# Sheet7.net
KiCad netlist of a schematic drawn in Altium Designer
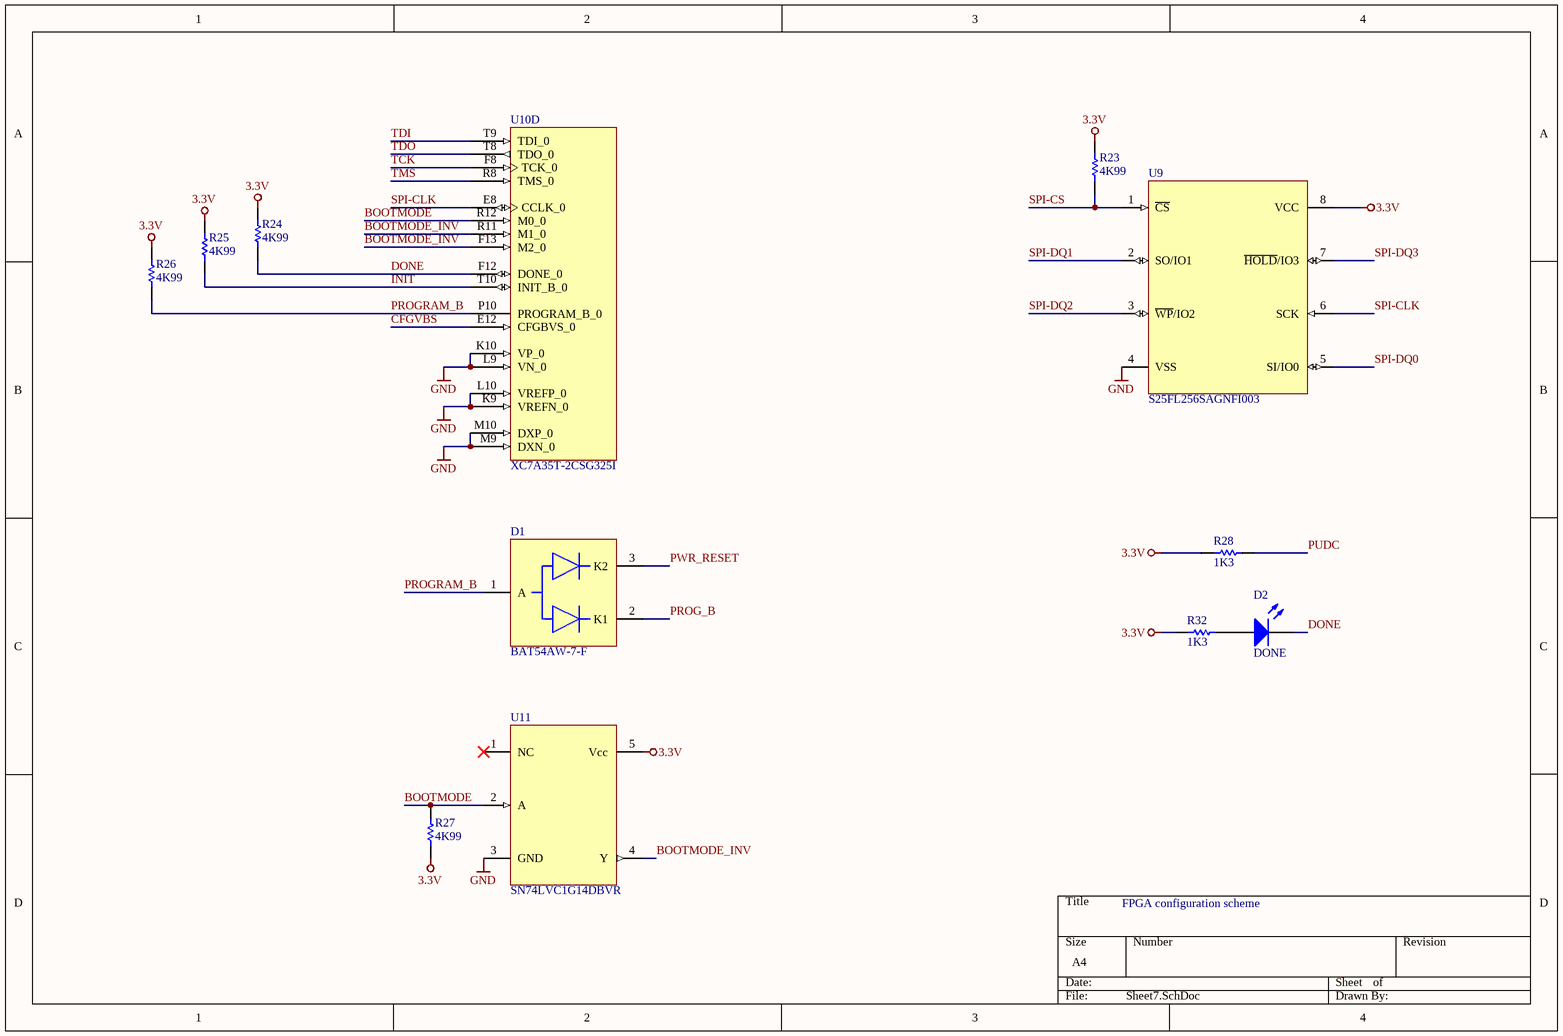
[diagram p0: Sheet7.SchDoc]

(export (version "E")
  (design (tool "Eeschema 10.0.6"))
  (components
    (comp (ref "D1")
      (value "BAT54AW-7-F")
      (footprint "BAT54AW-7-F")
      (description "SCHOTTKY BARRIER DIODE")
      (libsource (lib "Integrated_Library") (part "BAT54AW-7-F"))
    )
    (comp (ref "D2")
      (value "DONE")
      (footprint "LEDC2012X10N")
      (description "SMD chip LED")
      (libsource (lib "Integrated_Library") (part "LED0805"))
    )
    (comp (ref "R23")
      (value "4K99")
      (footprint "RESC1005X05N")
      (description "Ceramic Chip Resistor")
      (libsource (lib "Integrated_Library") (part "R0402"))
    )
    (comp (ref "R24")
      (value "4K99")
      (footprint "RESC1005X05N")
      (description "Ceramic Chip Resistor")
      (libsource (lib "Integrated_Library") (part "R0402"))
    )
    (comp (ref "R25")
      (value "4K99")
      (footprint "RESC1005X05N")
      (description "Ceramic Chip Resistor")
      (libsource (lib "Integrated_Library") (part "R0402"))
    )
    (comp (ref "R26")
      (value "4K99")
      (footprint "RESC1005X05N")
      (description "Ceramic Chip Resistor")
      (libsource (lib "Integrated_Library") (part "R0402"))
    )
    (comp (ref "R27")
      (value "4K99")
      (footprint "RESC1005X05N")
      (description "Ceramic Chip Resistor")
      (libsource (lib "Integrated_Library") (part "R0402"))
    )
    (comp (ref "R28")
      (value "1K3")
      (footprint "RESC1005X05N")
      (description "Ceramic Chip Resistor")
      (libsource (lib "Integrated_Library") (part "R0402"))
    )
    (comp (ref "R32")
      (value "1K3")
      (footprint "RESC1005X05N")
      (description "Ceramic Chip Resistor")
      (libsource (lib "Integrated_Library") (part "R0402"))
    )
    (comp (ref "U9")
      (value "S25FL256SAGNFI003")
      (footprint "S25FL256SAGNFI003")
      (description "256 Mbit (32 Mbyte)  3.0V SPI Flash Memory")
      (libsource (lib "Integrated_Library") (part "S25FL256SAGNFI003"))
    )
    (comp (ref "U10")
      (value "XC7A35T-2CSG325I")
      (footprint "XC7A35T-2CSG325I")
      (description "Artix-7 FPGA, 150 User I/Os, 4 GTP, 324-Ball BGA, Speed Grade 2, Industrial Grade, Pb-Free")
      (fields (field (name "MANUFACTURER") "Xilinx"))
      (libsource (lib "Integrated_Library") (part "XC7A35T-2CSG325I"))
    )
    (comp (ref "U11")
      (value "SN74LVC1G14DBVR")
      (footprint "SN74LVC1G14DBVR")
      (description "Single Schmitt-Trigger Inverter")
      (libsource (lib "Integrated_Library") (part "SN74LVC1G14DBVR"))
    )
  )
  (nets
    (net (code "1") (name "/BOOTMODE") (class "Default")
      (node (ref "R27") (pin "2") (pinfunction "2_2") (pintype "passive"))
      (node (ref "U10") (pin "R12") (pinfunction "M0_0_R12") (pintype "input"))
      (node (ref "U11") (pin "2") (pinfunction "A_2") (pintype "input"))
    )
    (net (code "2") (name "/BOOTMODE_INV") (class "Default")
      (node (ref "U10") (pin "F13") (pinfunction "M2_0_F13") (pintype "input"))
      (node (ref "U10") (pin "R11") (pinfunction "M1_0_R11") (pintype "input"))
      (node (ref "U11") (pin "4") (pinfunction "Y_4") (pintype "output"))
    )
    (net (code "3") (name "/CFGVBS") (class "Default")
      (node (ref "U10") (pin "E12") (pinfunction "CFGBVS_0_E12") (pintype "input"))
    )
    (net (code "4") (name "/DONE") (class "Default")
      (node (ref "D2") (pin "1") (pinfunction "K_1") (pintype "passive"))
      (node (ref "R24") (pin "2") (pinfunction "2_2") (pintype "passive"))
      (node (ref "U10") (pin "F12") (pinfunction "DONE_0_F12") (pintype "bidirectional"))
    )
    (net (code "5") (name "/INIT") (class "Default")
      (node (ref "R25") (pin "2") (pinfunction "2_2") (pintype "passive"))
      (node (ref "U10") (pin "T10") (pinfunction "INIT_B_0_T10") (pintype "bidirectional"))
    )
    (net (code "6") (name "/PROGRAM_B") (class "Default")
      (node (ref "D1") (pin "1") (pinfunction "A_1") (pintype "passive"))
      (node (ref "R26") (pin "2") (pinfunction "2_2") (pintype "passive"))
      (node (ref "U10") (pin "P10") (pinfunction "PROGRAM_B_0_P10") (pintype "passive"))
    )
    (net (code "7") (name "/PROG_B") (class "Default")
      (node (ref "D1") (pin "2") (pinfunction "K1_2") (pintype "passive"))
    )
    (net (code "8") (name "/PUDC") (class "Default")
      (node (ref "R28") (pin "1") (pinfunction "1_1") (pintype "passive"))
    )
    (net (code "9") (name "/PWR_RESET") (class "Default")
      (node (ref "D1") (pin "3") (pinfunction "K2_3") (pintype "passive"))
    )
    (net (code "10") (name "/SPI-CLK") (class "Default")
      (node (ref "U10") (pin "E8") (pinfunction "CCLK_0_E8") (pintype "bidirectional"))
      (node (ref "U9") (pin "6") (pinfunction "SCK_6") (pintype "input"))
    )
    (net (code "11") (name "/SPI-CS") (class "Default")
      (node (ref "R23") (pin "2") (pinfunction "2_2") (pintype "passive"))
      (node (ref "U9") (pin "1") (pinfunction "~{CS}_1") (pintype "input"))
    )
    (net (code "12") (name "/SPI-DQ0") (class "Default")
      (node (ref "U9") (pin "5") (pinfunction "SI/IO0_5") (pintype "bidirectional"))
    )
    (net (code "13") (name "/SPI-DQ1") (class "Default")
      (node (ref "U9") (pin "2") (pinfunction "SO/IO1_2") (pintype "bidirectional"))
    )
    (net (code "14") (name "/SPI-DQ2") (class "Default")
      (node (ref "U9") (pin "3") (pinfunction "~{WP}/IO2_3") (pintype "bidirectional"))
    )
    (net (code "15") (name "/SPI-DQ3") (class "Default")
      (node (ref "U9") (pin "7") (pinfunction "~{HOLD}/IO3_7") (pintype "bidirectional"))
    )
    (net (code "16") (name "/TCK") (class "Default")
      (node (ref "U10") (pin "F8") (pinfunction "TCK_0_F8") (pintype "input"))
    )
    (net (code "17") (name "/TDI") (class "Default")
      (node (ref "U10") (pin "T9") (pinfunction "TDI_0_T9") (pintype "input"))
    )
    (net (code "18") (name "/TDO") (class "Default")
      (node (ref "U10") (pin "T8") (pinfunction "TDO_0_T8") (pintype "output"))
    )
    (net (code "19") (name "/TMS") (class "Default")
      (node (ref "U10") (pin "R8") (pinfunction "TMS_0_R8") (pintype "input"))
    )
    (net (code "20") (name "3.3V") (class "Default")
      (node (ref "R23") (pin "1") (pinfunction "1_1") (pintype "passive"))
      (node (ref "R24") (pin "1") (pinfunction "1_1") (pintype "passive"))
      (node (ref "R25") (pin "1") (pinfunction "1_1") (pintype "passive"))
      (node (ref "R26") (pin "1") (pinfunction "1_1") (pintype "passive"))
      (node (ref "R27") (pin "1") (pinfunction "1_1") (pintype "passive"))
      (node (ref "R28") (pin "2") (pinfunction "2_2") (pintype "passive"))
      (node (ref "R32") (pin "2") (pinfunction "2_2") (pintype "passive"))
      (node (ref "U11") (pin "5") (pinfunction "Vcc_5") (pintype "power_in"))
      (node (ref "U9") (pin "8") (pinfunction "VCC_8") (pintype "power_in"))
    )
    (net (code "21") (name "GND") (class "Default")
      (node (ref "U10") (pin "K10") (pinfunction "VP_0_K10") (pintype "input"))
      (node (ref "U10") (pin "K9") (pinfunction "VREFN_0_K9") (pintype "input"))
      (node (ref "U10") (pin "L10") (pinfunction "VREFP_0_L10") (pintype "input"))
      (node (ref "U10") (pin "L9") (pinfunction "VN_0_L9") (pintype "input"))
      (node (ref "U10") (pin "M10") (pinfunction "DXP_0_M10") (pintype "input"))
      (node (ref "U10") (pin "M9") (pinfunction "DXN_0_M9") (pintype "input"))
      (node (ref "U11") (pin "3") (pinfunction "GND_3") (pintype "power_in"))
      (node (ref "U9") (pin "4") (pinfunction "VSS_4") (pintype "power_in"))
    )
    (net (code "22") (name "Net-(D2-A)") (class "Default")
      (node (ref "D2") (pin "2") (pinfunction "A_2") (pintype "passive"))
      (node (ref "R32") (pin "1") (pinfunction "1_1") (pintype "passive"))
    )
    (net (code "23") (name "unconnected-(U11-NC-Pad1)") (class "Default")
      (node (ref "U11") (pin "1") (pinfunction "NC_1") (pintype "passive+no_connect"))
    )
  )
)
